# Main.net
KiCad netlist of a schematic drawn in Altium Designer
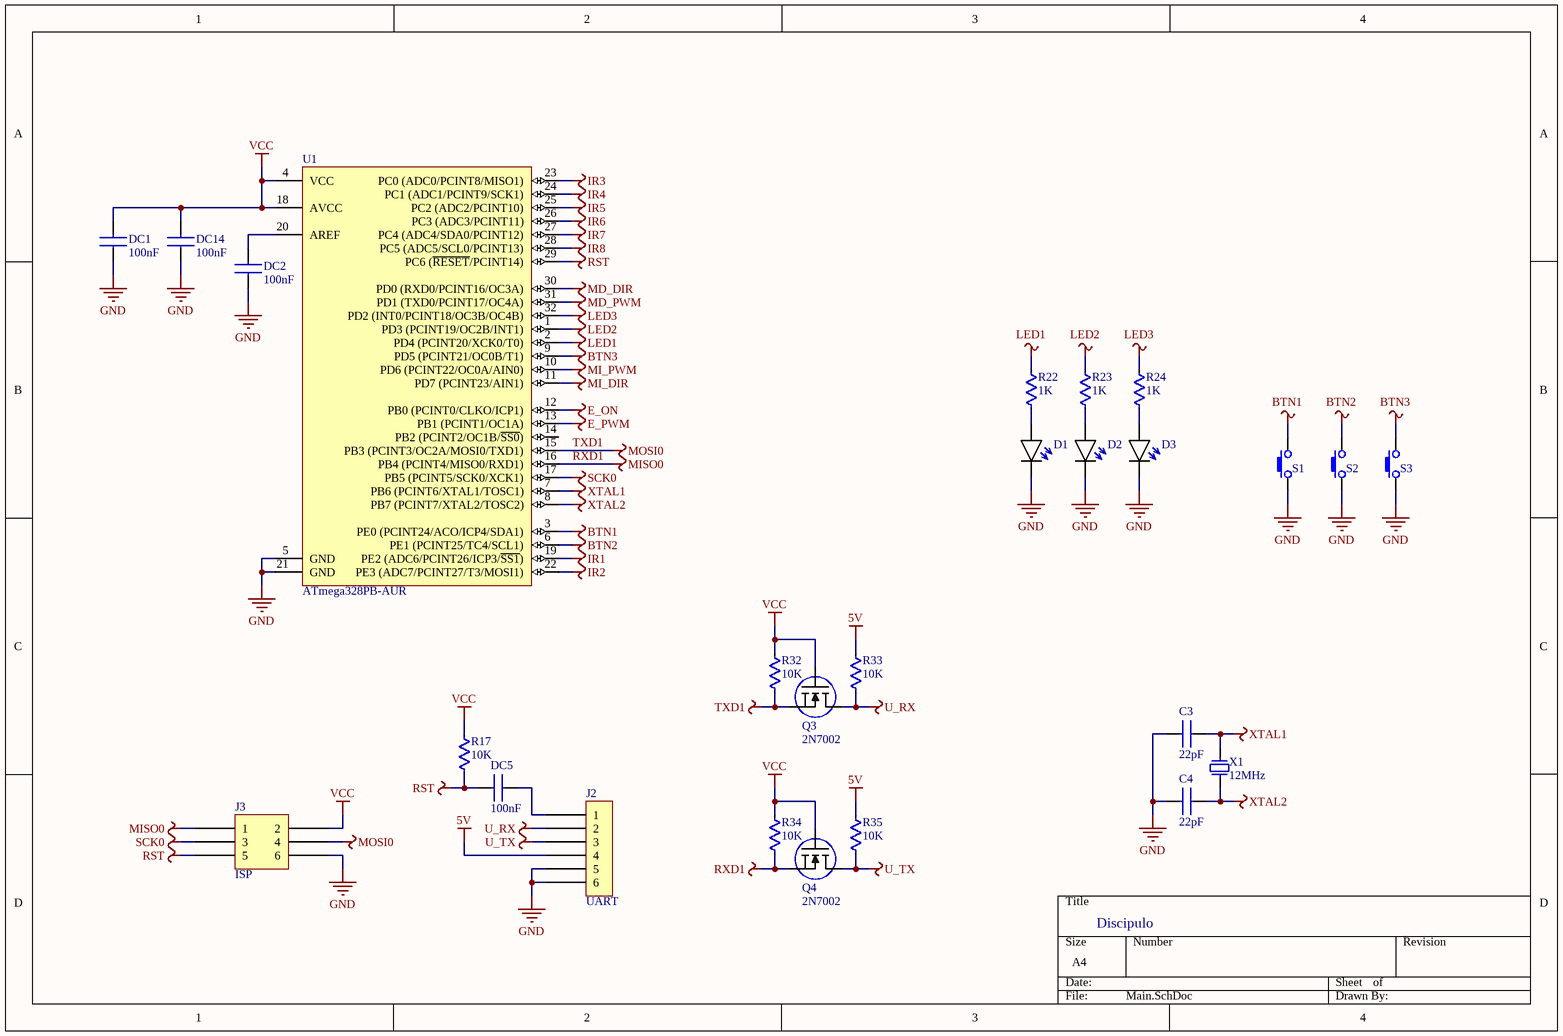
[diagram p0: Main.SchDoc]

(export (version "E")
  (design (tool "Eeschema 10.0.6"))
  (components
    (comp (ref "C3")
      (value "22pF")
      (footprint "C1206")
      (fields (field (name "Comment") "CAP-CER"))
      (libsource (lib "AltiumLibrary") (part "CAP-CER"))
    )
    (comp (ref "C4")
      (value "22pF")
      (footprint "C1206")
      (fields (field (name "Comment") "CAP-CER"))
      (libsource (lib "AltiumLibrary") (part "CAP-CER"))
    )
    (comp (ref "D1")
      (value "LED")
      (footprint "LED-3MM-YELLOW")
      (libsource (lib "AltiumLibrary") (part "LED"))
    )
    (comp (ref "D2")
      (value "LED")
      (footprint "LED-3MM-YELLOW")
      (libsource (lib "AltiumLibrary") (part "LED"))
    )
    (comp (ref "D3")
      (value "LED")
      (footprint "LED-3MM-YELLOW")
      (libsource (lib "AltiumLibrary") (part "LED"))
    )
    (comp (ref "DC1")
      (value "100nF")
      (footprint "C1206")
      (fields (field (name "Comment") "CAP-CER"))
      (libsource (lib "AltiumLibrary") (part "CAP-CER"))
    )
    (comp (ref "DC2")
      (value "100nF")
      (footprint "C1206")
      (fields (field (name "Comment") "CAP-CER"))
      (libsource (lib "AltiumLibrary") (part "CAP-CER"))
    )
    (comp (ref "DC5")
      (value "100nF")
      (footprint "C1206")
      (fields (field (name "Comment") "CAP-CER"))
      (libsource (lib "AltiumLibrary") (part "CAP-CER"))
    )
    (comp (ref "DC14")
      (value "100nF")
      (footprint "C1206")
      (fields (field (name "Comment") "CAP-CER"))
      (libsource (lib "AltiumLibrary") (part "CAP-CER"))
    )
    (comp (ref "J2")
      (value "UART")
      (footprint "Header 1x6")
      (libsource (lib "AltiumLibrary") (part "Header 1x6"))
    )
    (comp (ref "J3")
      (value "ISP")
      (footprint "HEADER 2x3")
      (libsource (lib "AltiumLibrary") (part "Header 2x3"))
    )
    (comp (ref "Q3")
      (value "2N7002")
      (footprint "SOT-23")
      (libsource (lib "AltiumLibrary") (part "N-MOSFET"))
    )
    (comp (ref "Q4")
      (value "2N7002")
      (footprint "SOT-23")
      (libsource (lib "AltiumLibrary") (part "N-MOSFET"))
    )
    (comp (ref "R17")
      (value "10K")
      (footprint "R1206")
      (fields (field (name "Comment") "RES"))
      (libsource (lib "AltiumLibrary") (part "RES"))
    )
    (comp (ref "R22")
      (value "1K")
      (footprint "R1206")
      (fields (field (name "Comment") "RES"))
      (libsource (lib "AltiumLibrary") (part "RES"))
    )
    (comp (ref "R23")
      (value "1K")
      (footprint "R1206")
      (fields (field (name "Comment") "RES"))
      (libsource (lib "AltiumLibrary") (part "RES"))
    )
    (comp (ref "R24")
      (value "1K")
      (footprint "R1206")
      (fields (field (name "Comment") "RES"))
      (libsource (lib "AltiumLibrary") (part "RES"))
    )
    (comp (ref "R32")
      (value "10K")
      (footprint "R1206")
      (fields (field (name "Comment") "RES"))
      (libsource (lib "AltiumLibrary") (part "RES"))
    )
    (comp (ref "R33")
      (value "10K")
      (footprint "R1206")
      (fields (field (name "Comment") "RES"))
      (libsource (lib "AltiumLibrary") (part "RES"))
    )
    (comp (ref "R34")
      (value "10K")
      (footprint "R1206")
      (fields (field (name "Comment") "RES"))
      (libsource (lib "AltiumLibrary") (part "RES"))
    )
    (comp (ref "R35")
      (value "10K")
      (footprint "R1206")
      (fields (field (name "Comment") "RES"))
      (libsource (lib "AltiumLibrary") (part "RES"))
    )
    (comp (ref "S1")
      (value "BUTTON")
      (footprint "TACT_SWITCH-SMALL-4PIN")
      (libsource (lib "AltiumLibrary") (part "BUTTON"))
    )
    (comp (ref "S2")
      (value "BUTTON")
      (footprint "TACT_SWITCH-SMALL-4PIN")
      (libsource (lib "AltiumLibrary") (part "BUTTON"))
    )
    (comp (ref "S3")
      (value "BUTTON")
      (footprint "TACT_SWITCH-SMALL-4PIN")
      (libsource (lib "AltiumLibrary") (part "BUTTON"))
    )
    (comp (ref "U1")
      (value "ATmega328PB-AUR")
      (footprint "32A_M")
      (libsource (lib "AltiumLibrary") (part "ATmega328PB-AUR"))
    )
    (comp (ref "X1")
      (value "XTAL")
      (footprint "HC-49/S")
      (fields (field (name "FREQUENCY") "12MHz"))
      (libsource (lib "AltiumLibrary") (part "XTAL"))
    )
  )
  (nets
    (net (code "1") (name "5V") (class "Default")
      (node (ref "J2") (pin "4") (pinfunction "4_4") (pintype "passive"))
      (node (ref "R33") (pin "2") (pintype "passive"))
      (node (ref "R35") (pin "2") (pintype "passive"))
    )
    (net (code "2") (name "BTN1") (class "Default")
      (node (ref "S1") (pin "2") (pintype "passive"))
      (node (ref "U1") (pin "3") (pinfunction "PE0_(PCINT24/ACO/ICP4/SDA1)_3") (pintype "bidirectional"))
    )
    (net (code "3") (name "BTN2") (class "Default")
      (node (ref "S2") (pin "2") (pintype "passive"))
      (node (ref "U1") (pin "6") (pinfunction "PE1_(PCINT25/TC4/SCL1)_6") (pintype "bidirectional"))
    )
    (net (code "4") (name "BTN3") (class "Default")
      (node (ref "S3") (pin "2") (pintype "passive"))
      (node (ref "U1") (pin "9") (pinfunction "PD5_(PCINT21/OC0B/T1)_9") (pintype "bidirectional"))
    )
    (net (code "5") (name "E_ON") (class "Default")
      (node (ref "U1") (pin "12") (pinfunction "PB0_(PCINT0/CLKO/ICP1)_12") (pintype "bidirectional"))
    )
    (net (code "6") (name "E_PWM") (class "Default")
      (node (ref "U1") (pin "13") (pinfunction "PB1_(PCINT1/OC1A)_13") (pintype "bidirectional"))
    )
    (net (code "7") (name "GND") (class "Default")
      (node (ref "C3") (pin "1") (pintype "passive"))
      (node (ref "C4") (pin "1") (pintype "passive"))
      (node (ref "D1") (pin "K") (pintype "passive"))
      (node (ref "D2") (pin "K") (pintype "passive"))
      (node (ref "D3") (pin "K") (pintype "passive"))
      (node (ref "DC1") (pin "2") (pintype "passive"))
      (node (ref "DC14") (pin "1") (pintype "passive"))
      (node (ref "DC2") (pin "2") (pintype "passive"))
      (node (ref "J2") (pin "5") (pinfunction "5_5") (pintype "passive"))
      (node (ref "J2") (pin "6") (pinfunction "6_6") (pintype "passive"))
      (node (ref "J3") (pin "6") (pinfunction "6_6") (pintype "passive"))
      (node (ref "S1") (pin "1") (pintype "passive"))
      (node (ref "S2") (pin "1") (pintype "passive"))
      (node (ref "S3") (pin "1") (pintype "passive"))
      (node (ref "U1") (pin "21") (pinfunction "GND_21") (pintype "power_in"))
      (node (ref "U1") (pin "5") (pinfunction "GND_5") (pintype "power_in"))
    )
    (net (code "8") (name "IR1") (class "Default")
      (node (ref "U1") (pin "19") (pinfunction "PE2_(ADC6/PCINT26/ICP3/~{SS1})_19") (pintype "bidirectional"))
    )
    (net (code "9") (name "IR2") (class "Default")
      (node (ref "U1") (pin "22") (pinfunction "PE3_(ADC7/PCINT27/T3/MOSI1)_22") (pintype "bidirectional"))
    )
    (net (code "10") (name "IR3") (class "Default")
      (node (ref "U1") (pin "23") (pinfunction "PC0_(ADC0/PCINT8/MISO1)_23") (pintype "bidirectional"))
    )
    (net (code "11") (name "IR4") (class "Default")
      (node (ref "U1") (pin "24") (pinfunction "PC1_(ADC1/PCINT9/SCK1)_24") (pintype "bidirectional"))
    )
    (net (code "12") (name "IR5") (class "Default")
      (node (ref "U1") (pin "25") (pinfunction "PC2_(ADC2/PCINT10)_25") (pintype "bidirectional"))
    )
    (net (code "13") (name "IR6") (class "Default")
      (node (ref "U1") (pin "26") (pinfunction "PC3_(ADC3/PCINT11)_26") (pintype "bidirectional"))
    )
    (net (code "14") (name "IR7") (class "Default")
      (node (ref "U1") (pin "27") (pinfunction "PC4_(ADC4/SDA0/PCINT12)_27") (pintype "bidirectional"))
    )
    (net (code "15") (name "IR8") (class "Default")
      (node (ref "U1") (pin "28") (pinfunction "PC5_(ADC5/SCL0/PCINT13)_28") (pintype "bidirectional"))
    )
    (net (code "16") (name "LED1") (class "Default")
      (node (ref "R22") (pin "2") (pintype "passive"))
      (node (ref "U1") (pin "2") (pinfunction "PD4_(PCINT20/XCK0/T0)_2") (pintype "bidirectional"))
    )
    (net (code "17") (name "LED2") (class "Default")
      (node (ref "R23") (pin "2") (pintype "passive"))
      (node (ref "U1") (pin "1") (pinfunction "PD3_(PCINT19/OC2B/INT1)_1") (pintype "bidirectional"))
    )
    (net (code "18") (name "LED3") (class "Default")
      (node (ref "R24") (pin "2") (pintype "passive"))
      (node (ref "U1") (pin "32") (pinfunction "PD2_(INT0/PCINT18/OC3B/OC4B)_32") (pintype "bidirectional"))
    )
    (net (code "19") (name "MD_DIR") (class "Default")
      (node (ref "U1") (pin "30") (pinfunction "PD0_(RXD0/PCINT16/OC3A)_30") (pintype "bidirectional"))
    )
    (net (code "20") (name "MD_PWM") (class "Default")
      (node (ref "U1") (pin "31") (pinfunction "PD1_(TXD0/PCINT17/OC4A)_31") (pintype "bidirectional"))
    )
    (net (code "21") (name "MISO0") (class "Default")
      (node (ref "J3") (pin "1") (pinfunction "1_1") (pintype "passive"))
      (node (ref "Q4") (pin "S") (pintype "passive"))
      (node (ref "R34") (pin "1") (pintype "passive"))
      (node (ref "U1") (pin "16") (pinfunction "PB4_(PCINT4/MISO0/RXD1)_16") (pintype "bidirectional"))
    )
    (net (code "22") (name "MI_DIR") (class "Default")
      (node (ref "U1") (pin "11") (pinfunction "PD7_(PCINT23/AIN1)_11") (pintype "bidirectional"))
    )
    (net (code "23") (name "MI_PWM") (class "Default")
      (node (ref "U1") (pin "10") (pinfunction "PD6_(PCINT22/OC0A/AIN0)_10") (pintype "bidirectional"))
    )
    (net (code "24") (name "MOSI0") (class "Default")
      (node (ref "J3") (pin "4") (pinfunction "4_4") (pintype "passive"))
      (node (ref "Q3") (pin "S") (pintype "passive"))
      (node (ref "R32") (pin "1") (pintype "passive"))
      (node (ref "U1") (pin "15") (pinfunction "PB3_(PCINT3/OC2A/MOSI0/TXD1)_15") (pintype "bidirectional"))
    )
    (net (code "25") (name "Net-(D1-PadA)") (class "Default")
      (node (ref "D1") (pin "A") (pintype "passive"))
      (node (ref "R22") (pin "1") (pintype "passive"))
    )
    (net (code "26") (name "Net-(D2-PadA)") (class "Default")
      (node (ref "D2") (pin "A") (pintype "passive"))
      (node (ref "R23") (pin "1") (pintype "passive"))
    )
    (net (code "27") (name "Net-(D3-PadA)") (class "Default")
      (node (ref "D3") (pin "A") (pintype "passive"))
      (node (ref "R24") (pin "1") (pintype "passive"))
    )
    (net (code "28") (name "Net-(DC5-Pad2)") (class "Default")
      (node (ref "DC5") (pin "2") (pintype "passive"))
      (node (ref "J2") (pin "1") (pinfunction "1_1") (pintype "passive"))
    )
    (net (code "29") (name "Net-(U1-AREF)") (class "Default")
      (node (ref "DC2") (pin "1") (pintype "passive"))
      (node (ref "U1") (pin "20") (pinfunction "AREF_20") (pintype "passive"))
    )
    (net (code "30") (name "RST") (class "Default")
      (node (ref "DC5") (pin "1") (pintype "passive"))
      (node (ref "J3") (pin "5") (pinfunction "5_5") (pintype "passive"))
      (node (ref "R17") (pin "1") (pintype "passive"))
      (node (ref "U1") (pin "29") (pinfunction "PC6_(~{RESET}/PCINT14)_29") (pintype "bidirectional"))
    )
    (net (code "31") (name "SCK0") (class "Default")
      (node (ref "J3") (pin "3") (pinfunction "3_3") (pintype "passive"))
      (node (ref "U1") (pin "17") (pinfunction "PB5_(PCINT5/SCK0/XCK1)_17") (pintype "bidirectional"))
    )
    (net (code "32") (name "U_RX") (class "Default")
      (node (ref "J2") (pin "2") (pinfunction "2_2") (pintype "passive"))
      (node (ref "Q3") (pin "D") (pintype "passive"))
      (node (ref "R33") (pin "1") (pintype "passive"))
    )
    (net (code "33") (name "U_TX") (class "Default")
      (node (ref "J2") (pin "3") (pinfunction "3_3") (pintype "passive"))
      (node (ref "Q4") (pin "D") (pintype "passive"))
      (node (ref "R35") (pin "1") (pintype "passive"))
    )
    (net (code "34") (name "VCC") (class "Default")
      (node (ref "DC1") (pin "1") (pintype "passive"))
      (node (ref "DC14") (pin "2") (pintype "passive"))
      (node (ref "J3") (pin "2") (pinfunction "2_2") (pintype "passive"))
      (node (ref "Q3") (pin "G") (pintype "passive"))
      (node (ref "Q4") (pin "G") (pintype "passive"))
      (node (ref "R17") (pin "2") (pintype "passive"))
      (node (ref "R32") (pin "2") (pintype "passive"))
      (node (ref "R34") (pin "2") (pintype "passive"))
      (node (ref "U1") (pin "18") (pinfunction "AVCC_18") (pintype "power_in"))
      (node (ref "U1") (pin "4") (pinfunction "VCC_4") (pintype "power_in"))
    )
    (net (code "35") (name "XTAL1") (class "Default")
      (node (ref "C3") (pin "2") (pintype "passive"))
      (node (ref "U1") (pin "7") (pinfunction "PB6_(PCINT6/XTAL1/TOSC1)_7") (pintype "bidirectional"))
      (node (ref "X1") (pin "2") (pintype "passive"))
    )
    (net (code "36") (name "XTAL2") (class "Default")
      (node (ref "C4") (pin "2") (pintype "passive"))
      (node (ref "U1") (pin "8") (pinfunction "PB7_(PCINT7/XTAL2/TOSC2)_8") (pintype "bidirectional"))
      (node (ref "X1") (pin "1") (pintype "passive"))
    )
    (net (code "37") (name "unconnected-(U1-PB2_(PCINT2{slash}OC1B{slash}~{SS0})-Pad14)") (class "Default")
      (node (ref "U1") (pin "14") (pinfunction "PB2_(PCINT2/OC1B/~{SS0})_14") (pintype "bidirectional"))
    )
  )
)
